# brain_system.net
KiCad netlist of a schematic drawn in EAGLE
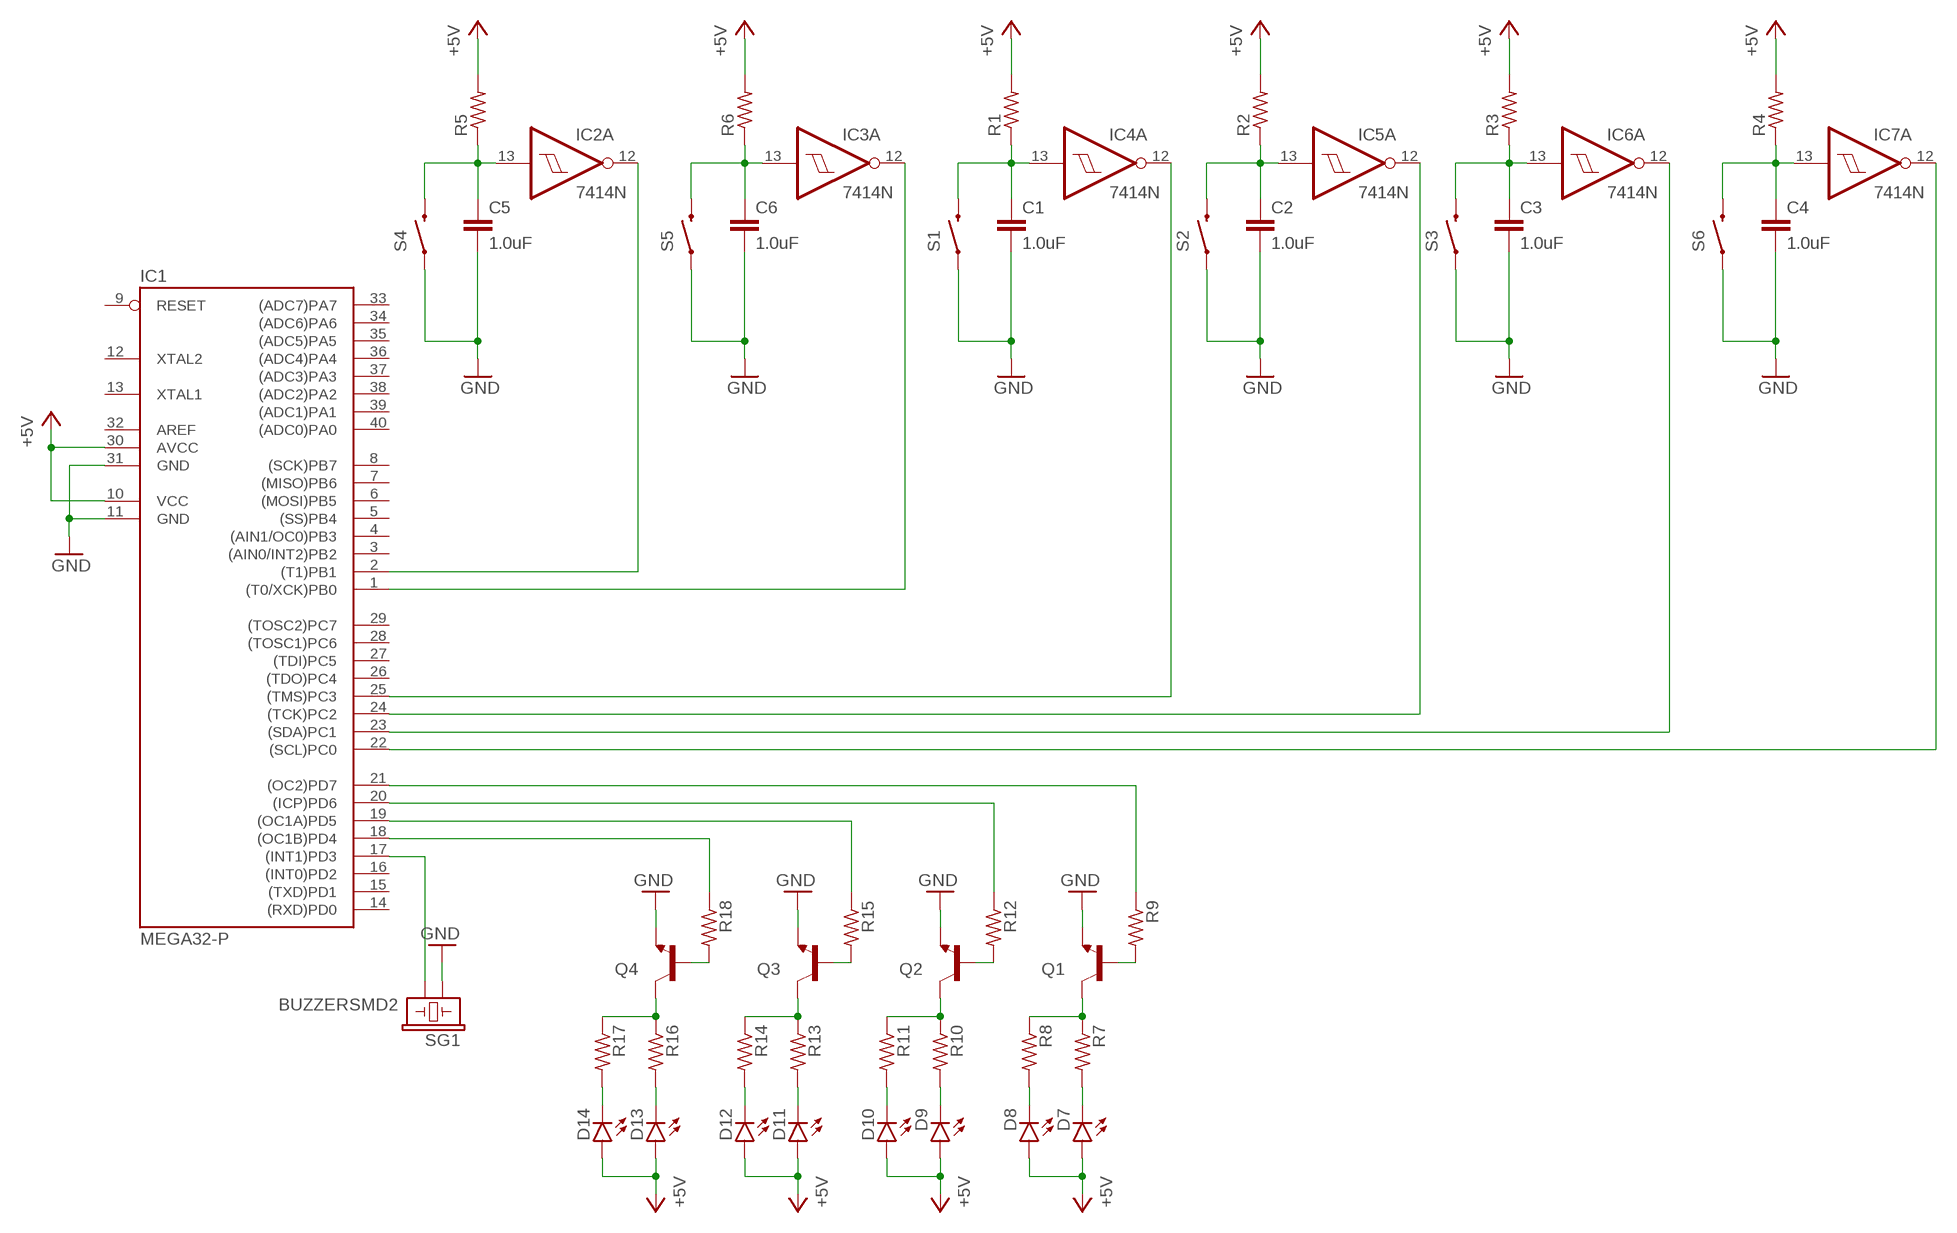
[diagram p0: schematic, sheet 1]

(export (version "E")
  (design (tool "Eeschema 10.0.6"))
  (components
    (comp (ref "C1")
      (value "1.0uF")
      (footprint "eagle-import:0402-CAP")
      (libsource (lib "eagle-import") (part "1.0UF-16V-10%(0402)"))
    )
    (comp (ref "C2")
      (value "1.0uF")
      (footprint "eagle-import:0402-CAP")
      (libsource (lib "eagle-import") (part "1.0UF-16V-10%(0402)"))
    )
    (comp (ref "C3")
      (value "1.0uF")
      (footprint "eagle-import:0402-CAP")
      (libsource (lib "eagle-import") (part "1.0UF-16V-10%(0402)"))
    )
    (comp (ref "C4")
      (value "1.0uF")
      (footprint "eagle-import:0402-CAP")
      (libsource (lib "eagle-import") (part "1.0UF-16V-10%(0402)"))
    )
    (comp (ref "C5")
      (value "1.0uF")
      (footprint "eagle-import:0402-CAP")
      (libsource (lib "eagle-import") (part "1.0UF-16V-10%(0402)"))
    )
    (comp (ref "C6")
      (value "1.0uF")
      (footprint "eagle-import:0402-CAP")
      (libsource (lib "eagle-import") (part "1.0UF-16V-10%(0402)"))
    )
    (comp (ref "D7")
      (value "LED5MM")
      (footprint "eagle-import:LED5MM")
      (libsource (lib "eagle-import") (part "LED5MM"))
    )
    (comp (ref "D8")
      (value "LED5MM")
      (footprint "eagle-import:LED5MM")
      (libsource (lib "eagle-import") (part "LED5MM"))
    )
    (comp (ref "D9")
      (value "LED5MM")
      (footprint "eagle-import:LED5MM")
      (libsource (lib "eagle-import") (part "LED5MM"))
    )
    (comp (ref "D10")
      (value "LED5MM")
      (footprint "eagle-import:LED5MM")
      (libsource (lib "eagle-import") (part "LED5MM"))
    )
    (comp (ref "D11")
      (value "LED5MM")
      (footprint "eagle-import:LED5MM")
      (libsource (lib "eagle-import") (part "LED5MM"))
    )
    (comp (ref "D12")
      (value "LED5MM")
      (footprint "eagle-import:LED5MM")
      (libsource (lib "eagle-import") (part "LED5MM"))
    )
    (comp (ref "D13")
      (value "LED5MM")
      (footprint "eagle-import:LED5MM")
      (libsource (lib "eagle-import") (part "LED5MM"))
    )
    (comp (ref "D14")
      (value "LED5MM")
      (footprint "eagle-import:LED5MM")
      (libsource (lib "eagle-import") (part "LED5MM"))
    )
    (comp (ref "IC1")
      (value "MEGA32-P")
      (footprint "eagle-import:DIL40")
      (fields (field (name "MPN") "ATMEGA32-16PU"))
      (libsource (lib "eagle-import") (part "MEGA32-P"))
    )
    (comp (ref "IC2")
      (value "7414N")
      (footprint "eagle-import:DIL14")
      (libsource (lib "eagle-import") (part "7414N"))
    )
    (comp (ref "IC3")
      (value "7414N")
      (footprint "eagle-import:DIL14")
      (libsource (lib "eagle-import") (part "7414N"))
    )
    (comp (ref "IC4")
      (value "7414N")
      (footprint "eagle-import:DIL14")
      (libsource (lib "eagle-import") (part "7414N"))
    )
    (comp (ref "IC5")
      (value "7414N")
      (footprint "eagle-import:DIL14")
      (libsource (lib "eagle-import") (part "7414N"))
    )
    (comp (ref "IC6")
      (value "7414N")
      (footprint "eagle-import:DIL14")
      (libsource (lib "eagle-import") (part "7414N"))
    )
    (comp (ref "IC7")
      (value "7414N")
      (footprint "eagle-import:DIL14")
      (libsource (lib "eagle-import") (part "7414N"))
    )
    (comp (ref "Q1")
      (value "TRANSISTOR_NPNTO92")
      (footprint "eagle-import:TO-92")
      (libsource (lib "eagle-import") (part "TRANSISTOR_NPNTO92"))
    )
    (comp (ref "Q2")
      (value "TRANSISTOR_NPNTO92")
      (footprint "eagle-import:TO-92")
      (libsource (lib "eagle-import") (part "TRANSISTOR_NPNTO92"))
    )
    (comp (ref "Q3")
      (value "TRANSISTOR_NPNTO92")
      (footprint "eagle-import:TO-92")
      (libsource (lib "eagle-import") (part "TRANSISTOR_NPNTO92"))
    )
    (comp (ref "Q4")
      (value "TRANSISTOR_NPNTO92")
      (footprint "eagle-import:TO-92")
      (libsource (lib "eagle-import") (part "TRANSISTOR_NPNTO92"))
    )
    (comp (ref "R1")
      (value "R-US_0204/5")
      (footprint "eagle-import:0204_5")
      (libsource (lib "eagle-import") (part "R-US_0204/5"))
    )
    (comp (ref "R2")
      (value "R-US_0204/5")
      (footprint "eagle-import:0204_5")
      (libsource (lib "eagle-import") (part "R-US_0204/5"))
    )
    (comp (ref "R3")
      (value "R-US_0204/5")
      (footprint "eagle-import:0204_5")
      (libsource (lib "eagle-import") (part "R-US_0204/5"))
    )
    (comp (ref "R4")
      (value "R-US_0204/5")
      (footprint "eagle-import:0204_5")
      (libsource (lib "eagle-import") (part "R-US_0204/5"))
    )
    (comp (ref "R5")
      (value "R-US_0204/5")
      (footprint "eagle-import:0204_5")
      (libsource (lib "eagle-import") (part "R-US_0204/5"))
    )
    (comp (ref "R6")
      (value "R-US_0204/5")
      (footprint "eagle-import:0204_5")
      (libsource (lib "eagle-import") (part "R-US_0204/5"))
    )
    (comp (ref "R7")
      (value "R-US_0204/5")
      (footprint "eagle-import:0204_5")
      (libsource (lib "eagle-import") (part "R-US_0204/5"))
    )
    (comp (ref "R8")
      (value "R-US_0204/5")
      (footprint "eagle-import:0204_5")
      (libsource (lib "eagle-import") (part "R-US_0204/5"))
    )
    (comp (ref "R9")
      (value "R-US_0204/5")
      (footprint "eagle-import:0204_5")
      (libsource (lib "eagle-import") (part "R-US_0204/5"))
    )
    (comp (ref "R10")
      (value "R-US_0204/5")
      (footprint "eagle-import:0204_5")
      (libsource (lib "eagle-import") (part "R-US_0204/5"))
    )
    (comp (ref "R11")
      (value "R-US_0204/5")
      (footprint "eagle-import:0204_5")
      (libsource (lib "eagle-import") (part "R-US_0204/5"))
    )
    (comp (ref "R12")
      (value "R-US_0204/5")
      (footprint "eagle-import:0204_5")
      (libsource (lib "eagle-import") (part "R-US_0204/5"))
    )
    (comp (ref "R13")
      (value "R-US_0204/5")
      (footprint "eagle-import:0204_5")
      (libsource (lib "eagle-import") (part "R-US_0204/5"))
    )
    (comp (ref "R14")
      (value "R-US_0204/5")
      (footprint "eagle-import:0204_5")
      (libsource (lib "eagle-import") (part "R-US_0204/5"))
    )
    (comp (ref "R15")
      (value "R-US_0204/5")
      (footprint "eagle-import:0204_5")
      (libsource (lib "eagle-import") (part "R-US_0204/5"))
    )
    (comp (ref "R16")
      (value "R-US_0204/5")
      (footprint "eagle-import:0204_5")
      (libsource (lib "eagle-import") (part "R-US_0204/5"))
    )
    (comp (ref "R17")
      (value "R-US_0204/5")
      (footprint "eagle-import:0204_5")
      (libsource (lib "eagle-import") (part "R-US_0204/5"))
    )
    (comp (ref "R18")
      (value "R-US_0204/5")
      (footprint "eagle-import:0204_5")
      (libsource (lib "eagle-import") (part "R-US_0204/5"))
    )
    (comp (ref "S1")
      (value "SWITCH-MOMENTARY-2PTH")
      (footprint "eagle-import:TACTILE-PTH")
      (libsource (lib "eagle-import") (part "SWITCH-MOMENTARY-2PTH"))
    )
    (comp (ref "S2")
      (value "SWITCH-MOMENTARY-2PTH")
      (footprint "eagle-import:TACTILE-PTH")
      (libsource (lib "eagle-import") (part "SWITCH-MOMENTARY-2PTH"))
    )
    (comp (ref "S3")
      (value "SWITCH-MOMENTARY-2PTH")
      (footprint "eagle-import:TACTILE-PTH")
      (libsource (lib "eagle-import") (part "SWITCH-MOMENTARY-2PTH"))
    )
    (comp (ref "S4")
      (value "SWITCH-MOMENTARY-2PTH")
      (footprint "eagle-import:TACTILE-PTH")
      (libsource (lib "eagle-import") (part "SWITCH-MOMENTARY-2PTH"))
    )
    (comp (ref "S5")
      (value "SWITCH-MOMENTARY-2PTH")
      (footprint "eagle-import:TACTILE-PTH")
      (libsource (lib "eagle-import") (part "SWITCH-MOMENTARY-2PTH"))
    )
    (comp (ref "S6")
      (value "SWITCH-MOMENTARY-2PTH")
      (footprint "eagle-import:TACTILE-PTH")
      (libsource (lib "eagle-import") (part "SWITCH-MOMENTARY-2PTH"))
    )
    (comp (ref "SG1")
      (value "BUZZERSMD2")
      (footprint "eagle-import:BUZZER-CCV")
      (libsource (lib "eagle-import") (part "BUZZERSMD2"))
    )
  )
  (nets
    (net (code "1") (name "+5V") (class "Default")
      (node (ref "D10") (pin "A") (pinfunction "A_A") (pintype "passive"))
      (node (ref "D11") (pin "A") (pinfunction "A_A") (pintype "passive"))
      (node (ref "D12") (pin "A") (pinfunction "A_A") (pintype "passive"))
      (node (ref "D13") (pin "A") (pinfunction "A_A") (pintype "passive"))
      (node (ref "D14") (pin "A") (pinfunction "A_A") (pintype "passive"))
      (node (ref "D7") (pin "A") (pinfunction "A_A") (pintype "passive"))
      (node (ref "D8") (pin "A") (pinfunction "A_A") (pintype "passive"))
      (node (ref "D9") (pin "A") (pinfunction "A_A") (pintype "passive"))
      (node (ref "IC1") (pin "10") (pinfunction "VCC_10") (pintype "power_in"))
      (node (ref "IC1") (pin "30") (pinfunction "AVCC_30") (pintype "power_in"))
      (node (ref "R1") (pin "2") (pinfunction "2_2") (pintype "passive"))
      (node (ref "R2") (pin "2") (pinfunction "2_2") (pintype "passive"))
      (node (ref "R3") (pin "2") (pinfunction "2_2") (pintype "passive"))
      (node (ref "R4") (pin "2") (pinfunction "2_2") (pintype "passive"))
      (node (ref "R5") (pin "2") (pinfunction "2_2") (pintype "passive"))
      (node (ref "R6") (pin "2") (pinfunction "2_2") (pintype "passive"))
    )
    (net (code "2") (name "GND") (class "Default")
      (node (ref "C1") (pin "2") (pinfunction "2_2") (pintype "passive"))
      (node (ref "C2") (pin "2") (pinfunction "2_2") (pintype "passive"))
      (node (ref "C3") (pin "2") (pinfunction "2_2") (pintype "passive"))
      (node (ref "C4") (pin "2") (pinfunction "2_2") (pintype "passive"))
      (node (ref "C5") (pin "2") (pinfunction "2_2") (pintype "passive"))
      (node (ref "C6") (pin "2") (pinfunction "2_2") (pintype "passive"))
      (node (ref "IC1") (pin "11") (pinfunction "GND_11") (pintype "power_in"))
      (node (ref "IC1") (pin "31") (pinfunction "GND_31") (pintype "power_in"))
      (node (ref "Q1") (pin "1") (pinfunction "E_1") (pintype "passive"))
      (node (ref "Q2") (pin "1") (pinfunction "E_1") (pintype "passive"))
      (node (ref "Q3") (pin "1") (pinfunction "E_1") (pintype "passive"))
      (node (ref "Q4") (pin "1") (pinfunction "E_1") (pintype "passive"))
      (node (ref "S1") (pin "1") (pinfunction "1_1") (pintype "passive"))
      (node (ref "S2") (pin "1") (pinfunction "1_1") (pintype "passive"))
      (node (ref "S3") (pin "1") (pinfunction "1_1") (pintype "passive"))
      (node (ref "S4") (pin "1") (pinfunction "1_1") (pintype "passive"))
      (node (ref "S5") (pin "1") (pinfunction "1_1") (pintype "passive"))
      (node (ref "S6") (pin "1") (pinfunction "1_1") (pintype "passive"))
      (node (ref "SG1") (pin "+") (pinfunction "1_+") (pintype "passive"))
    )
    (net (code "3") (name "Net-(D7-C)") (class "Default")
      (node (ref "D7") (pin "K") (pinfunction "C_K") (pintype "passive"))
      (node (ref "R7") (pin "2") (pinfunction "2_2") (pintype "passive"))
    )
    (net (code "4") (name "Net-(D8-C)") (class "Default")
      (node (ref "D8") (pin "K") (pinfunction "C_K") (pintype "passive"))
      (node (ref "R8") (pin "2") (pinfunction "2_2") (pintype "passive"))
    )
    (net (code "5") (name "Net-(D9-C)") (class "Default")
      (node (ref "D9") (pin "K") (pinfunction "C_K") (pintype "passive"))
      (node (ref "R10") (pin "2") (pinfunction "2_2") (pintype "passive"))
    )
    (net (code "6") (name "Net-(D10-C)") (class "Default")
      (node (ref "D10") (pin "K") (pinfunction "C_K") (pintype "passive"))
      (node (ref "R11") (pin "2") (pinfunction "2_2") (pintype "passive"))
    )
    (net (code "7") (name "Net-(D11-C)") (class "Default")
      (node (ref "D11") (pin "K") (pinfunction "C_K") (pintype "passive"))
      (node (ref "R13") (pin "2") (pinfunction "2_2") (pintype "passive"))
    )
    (net (code "8") (name "Net-(D12-C)") (class "Default")
      (node (ref "D12") (pin "K") (pinfunction "C_K") (pintype "passive"))
      (node (ref "R14") (pin "2") (pinfunction "2_2") (pintype "passive"))
    )
    (net (code "9") (name "Net-(D13-C)") (class "Default")
      (node (ref "D13") (pin "K") (pinfunction "C_K") (pintype "passive"))
      (node (ref "R16") (pin "2") (pinfunction "2_2") (pintype "passive"))
    )
    (net (code "10") (name "Net-(D14-C)") (class "Default")
      (node (ref "D14") (pin "K") (pinfunction "C_K") (pintype "passive"))
      (node (ref "R17") (pin "2") (pinfunction "2_2") (pintype "passive"))
    )
    (net (code "11") (name "Net-(IC1-(ICP)PD6)") (class "Default")
      (node (ref "IC1") (pin "20") (pinfunction "(ICP)PD6_20") (pintype "bidirectional"))
      (node (ref "R12") (pin "1") (pinfunction "1_1") (pintype "passive"))
    )
    (net (code "12") (name "Net-(IC1-(INT1)PD3)") (class "Default")
      (node (ref "IC1") (pin "17") (pinfunction "(INT1)PD3_17") (pintype "bidirectional"))
      (node (ref "SG1") (pin "-") (pinfunction "2_-") (pintype "passive"))
    )
    (net (code "13") (name "Net-(IC1-(OC1A)PD5)") (class "Default")
      (node (ref "IC1") (pin "19") (pinfunction "(OC1A)PD5_19") (pintype "bidirectional"))
      (node (ref "R15") (pin "1") (pinfunction "1_1") (pintype "passive"))
    )
    (net (code "14") (name "Net-(IC1-(OC1B)PD4)") (class "Default")
      (node (ref "IC1") (pin "18") (pinfunction "(OC1B)PD4_18") (pintype "bidirectional"))
      (node (ref "R18") (pin "1") (pinfunction "1_1") (pintype "passive"))
    )
    (net (code "15") (name "Net-(IC1-(OC2)PD7)") (class "Default")
      (node (ref "IC1") (pin "21") (pinfunction "(OC2)PD7_21") (pintype "bidirectional"))
      (node (ref "R9") (pin "1") (pinfunction "1_1") (pintype "passive"))
    )
    (net (code "16") (name "Net-(IC1-(SCL)PC0)") (class "Default")
      (node (ref "IC1") (pin "22") (pinfunction "(SCL)PC0_22") (pintype "bidirectional"))
      (node (ref "IC7") (pin "12") (pinfunction "O_12") (pintype "output"))
    )
    (net (code "17") (name "Net-(IC1-(SDA)PC1)") (class "Default")
      (node (ref "IC1") (pin "23") (pinfunction "(SDA)PC1_23") (pintype "bidirectional"))
      (node (ref "IC6") (pin "12") (pinfunction "O_12") (pintype "output"))
    )
    (net (code "18") (name "Net-(IC1-(T0{slash}XCK)PB0)") (class "Default")
      (node (ref "IC1") (pin "1") (pinfunction "(T0/XCK)PB0_1") (pintype "bidirectional"))
      (node (ref "IC3") (pin "12") (pinfunction "O_12") (pintype "output"))
    )
    (net (code "19") (name "Net-(IC1-(T1)PB1)") (class "Default")
      (node (ref "IC1") (pin "2") (pinfunction "(T1)PB1_2") (pintype "bidirectional"))
      (node (ref "IC2") (pin "12") (pinfunction "O_12") (pintype "output"))
    )
    (net (code "20") (name "Net-(IC1-(TCK)PC2)") (class "Default")
      (node (ref "IC1") (pin "24") (pinfunction "(TCK)PC2_24") (pintype "bidirectional"))
      (node (ref "IC5") (pin "12") (pinfunction "O_12") (pintype "output"))
    )
    (net (code "21") (name "Net-(IC1-(TMS)PC3)") (class "Default")
      (node (ref "IC1") (pin "25") (pinfunction "(TMS)PC3_25") (pintype "bidirectional"))
      (node (ref "IC4") (pin "12") (pinfunction "O_12") (pintype "output"))
    )
    (net (code "22") (name "Net-(IC2A-I)") (class "Default")
      (node (ref "C5") (pin "1") (pinfunction "1_1") (pintype "passive"))
      (node (ref "IC2") (pin "13") (pinfunction "I_13") (pintype "input"))
      (node (ref "R5") (pin "1") (pinfunction "1_1") (pintype "passive"))
      (node (ref "S4") (pin "3") (pinfunction "2_3") (pintype "passive"))
    )
    (net (code "23") (name "Net-(IC3A-I)") (class "Default")
      (node (ref "C6") (pin "1") (pinfunction "1_1") (pintype "passive"))
      (node (ref "IC3") (pin "13") (pinfunction "I_13") (pintype "input"))
      (node (ref "R6") (pin "1") (pinfunction "1_1") (pintype "passive"))
      (node (ref "S5") (pin "3") (pinfunction "2_3") (pintype "passive"))
    )
    (net (code "24") (name "Net-(IC4A-I)") (class "Default")
      (node (ref "C1") (pin "1") (pinfunction "1_1") (pintype "passive"))
      (node (ref "IC4") (pin "13") (pinfunction "I_13") (pintype "input"))
      (node (ref "R1") (pin "1") (pinfunction "1_1") (pintype "passive"))
      (node (ref "S1") (pin "3") (pinfunction "2_3") (pintype "passive"))
    )
    (net (code "25") (name "Net-(IC5A-I)") (class "Default")
      (node (ref "C2") (pin "1") (pinfunction "1_1") (pintype "passive"))
      (node (ref "IC5") (pin "13") (pinfunction "I_13") (pintype "input"))
      (node (ref "R2") (pin "1") (pinfunction "1_1") (pintype "passive"))
      (node (ref "S2") (pin "3") (pinfunction "2_3") (pintype "passive"))
    )
    (net (code "26") (name "Net-(IC6A-I)") (class "Default")
      (node (ref "C3") (pin "1") (pinfunction "1_1") (pintype "passive"))
      (node (ref "IC6") (pin "13") (pinfunction "I_13") (pintype "input"))
      (node (ref "R3") (pin "1") (pinfunction "1_1") (pintype "passive"))
      (node (ref "S3") (pin "3") (pinfunction "2_3") (pintype "passive"))
    )
    (net (code "27") (name "Net-(IC7A-I)") (class "Default")
      (node (ref "C4") (pin "1") (pinfunction "1_1") (pintype "passive"))
      (node (ref "IC7") (pin "13") (pinfunction "I_13") (pintype "input"))
      (node (ref "R4") (pin "1") (pinfunction "1_1") (pintype "passive"))
      (node (ref "S6") (pin "3") (pinfunction "2_3") (pintype "passive"))
    )
    (net (code "28") (name "Net-(Q1-B)") (class "Default")
      (node (ref "Q1") (pin "2") (pinfunction "B_2") (pintype "passive"))
      (node (ref "R9") (pin "2") (pinfunction "2_2") (pintype "passive"))
    )
    (net (code "29") (name "Net-(Q1-C)") (class "Default")
      (node (ref "Q1") (pin "3") (pinfunction "C_3") (pintype "passive"))
      (node (ref "R7") (pin "1") (pinfunction "1_1") (pintype "passive"))
      (node (ref "R8") (pin "1") (pinfunction "1_1") (pintype "passive"))
    )
    (net (code "30") (name "Net-(Q2-B)") (class "Default")
      (node (ref "Q2") (pin "2") (pinfunction "B_2") (pintype "passive"))
      (node (ref "R12") (pin "2") (pinfunction "2_2") (pintype "passive"))
    )
    (net (code "31") (name "Net-(Q2-C)") (class "Default")
      (node (ref "Q2") (pin "3") (pinfunction "C_3") (pintype "passive"))
      (node (ref "R10") (pin "1") (pinfunction "1_1") (pintype "passive"))
      (node (ref "R11") (pin "1") (pinfunction "1_1") (pintype "passive"))
    )
    (net (code "32") (name "Net-(Q3-B)") (class "Default")
      (node (ref "Q3") (pin "2") (pinfunction "B_2") (pintype "passive"))
      (node (ref "R15") (pin "2") (pinfunction "2_2") (pintype "passive"))
    )
    (net (code "33") (name "Net-(Q3-C)") (class "Default")
      (node (ref "Q3") (pin "3") (pinfunction "C_3") (pintype "passive"))
      (node (ref "R13") (pin "1") (pinfunction "1_1") (pintype "passive"))
      (node (ref "R14") (pin "1") (pinfunction "1_1") (pintype "passive"))
    )
    (net (code "34") (name "Net-(Q4-B)") (class "Default")
      (node (ref "Q4") (pin "2") (pinfunction "B_2") (pintype "passive"))
      (node (ref "R18") (pin "2") (pinfunction "2_2") (pintype "passive"))
    )
    (net (code "35") (name "Net-(Q4-C)") (class "Default")
      (node (ref "Q4") (pin "3") (pinfunction "C_3") (pintype "passive"))
      (node (ref "R16") (pin "1") (pinfunction "1_1") (pintype "passive"))
      (node (ref "R17") (pin "1") (pinfunction "1_1") (pintype "passive"))
    )
    (net (code "36") (name "unconnected-(IC1-(ADC0)PA0-Pad40)") (class "Default")
      (node (ref "IC1") (pin "40") (pinfunction "(ADC0)PA0_40") (pintype "bidirectional"))
    )
    (net (code "37") (name "unconnected-(IC1-(ADC1)PA1-Pad39)") (class "Default")
      (node (ref "IC1") (pin "39") (pinfunction "(ADC1)PA1_39") (pintype "bidirectional"))
    )
    (net (code "38") (name "unconnected-(IC1-(ADC2)PA2-Pad38)") (class "Default")
      (node (ref "IC1") (pin "38") (pinfunction "(ADC2)PA2_38") (pintype "bidirectional"))
    )
    (net (code "39") (name "unconnected-(IC1-(ADC3)PA3-Pad37)") (class "Default")
      (node (ref "IC1") (pin "37") (pinfunction "(ADC3)PA3_37") (pintype "bidirectional"))
    )
    (net (code "40") (name "unconnected-(IC1-(ADC4)PA4-Pad36)") (class "Default")
      (node (ref "IC1") (pin "36") (pinfunction "(ADC4)PA4_36") (pintype "bidirectional"))
    )
    (net (code "41") (name "unconnected-(IC1-(ADC5)PA5-Pad35)") (class "Default")
      (node (ref "IC1") (pin "35") (pinfunction "(ADC5)PA5_35") (pintype "bidirectional"))
    )
    (net (code "42") (name "unconnected-(IC1-(ADC6)PA6-Pad34)") (class "Default")
      (node (ref "IC1") (pin "34") (pinfunction "(ADC6)PA6_34") (pintype "bidirectional"))
    )
    (net (code "43") (name "unconnected-(IC1-(ADC7)PA7-Pad33)") (class "Default")
      (node (ref "IC1") (pin "33") (pinfunction "(ADC7)PA7_33") (pintype "bidirectional"))
    )
    (net (code "44") (name "unconnected-(IC1-(AIN0{slash}INT2)PB2-Pad3)") (class "Default")
      (node (ref "IC1") (pin "3") (pinfunction "(AIN0/INT2)PB2_3") (pintype "bidirectional"))
    )
    (net (code "45") (name "unconnected-(IC1-(AIN1{slash}OC0)PB3-Pad4)") (class "Default")
      (node (ref "IC1") (pin "4") (pinfunction "(AIN1/OC0)PB3_4") (pintype "bidirectional"))
    )
    (net (code "46") (name "unconnected-(IC1-(INT0)PD2-Pad16)") (class "Default")
      (node (ref "IC1") (pin "16") (pinfunction "(INT0)PD2_16") (pintype "bidirectional"))
    )
    (net (code "47") (name "unconnected-(IC1-(MISO)PB6-Pad7)") (class "Default")
      (node (ref "IC1") (pin "7") (pinfunction "(MISO)PB6_7") (pintype "bidirectional"))
    )
    (net (code "48") (name "unconnected-(IC1-(MOSI)PB5-Pad6)") (class "Default")
      (node (ref "IC1") (pin "6") (pinfunction "(MOSI)PB5_6") (pintype "bidirectional"))
    )
    (net (code "49") (name "unconnected-(IC1-(RXD)PD0-Pad14)") (class "Default")
      (node (ref "IC1") (pin "14") (pinfunction "(RXD)PD0_14") (pintype "bidirectional"))
    )
    (net (code "50") (name "unconnected-(IC1-(SCK)PB7-Pad8)") (class "Default")
      (node (ref "IC1") (pin "8") (pinfunction "(SCK)PB7_8") (pintype "bidirectional"))
    )
    (net (code "51") (name "unconnected-(IC1-(SS)PB4-Pad5)") (class "Default")
      (node (ref "IC1") (pin "5") (pinfunction "(SS)PB4_5") (pintype "bidirectional"))
    )
    (net (code "52") (name "unconnected-(IC1-(TDI)PC5-Pad27)") (class "Default")
      (node (ref "IC1") (pin "27") (pinfunction "(TDI)PC5_27") (pintype "bidirectional"))
    )
    (net (code "53") (name "unconnected-(IC1-(TDO)PC4-Pad26)") (class "Default")
      (node (ref "IC1") (pin "26") (pinfunction "(TDO)PC4_26") (pintype "bidirectional"))
    )
    (net (code "54") (name "unconnected-(IC1-(TOSC1)PC6-Pad28)") (class "Default")
      (node (ref "IC1") (pin "28") (pinfunction "(TOSC1)PC6_28") (pintype "bidirectional"))
    )
    (net (code "55") (name "unconnected-(IC1-(TOSC2)PC7-Pad29)") (class "Default")
      (node (ref "IC1") (pin "29") (pinfunction "(TOSC2)PC7_29") (pintype "bidirectional"))
    )
    (net (code "56") (name "unconnected-(IC1-(TXD)PD1-Pad15)") (class "Default")
      (node (ref "IC1") (pin "15") (pinfunction "(TXD)PD1_15") (pintype "bidirectional"))
    )
    (net (code "57") (name "unconnected-(IC1-AREF-Pad32)") (class "Default")
      (node (ref "IC1") (pin "32") (pinfunction "AREF_32") (pintype "passive"))
    )
    (net (code "58") (name "unconnected-(IC1-RESET-Pad9)") (class "Default")
      (node (ref "IC1") (pin "9") (pinfunction "RESET_9") (pintype "input"))
    )
    (net (code "59") (name "unconnected-(IC1-XTAL1-Pad13)") (class "Default")
      (node (ref "IC1") (pin "13") (pinfunction "XTAL1_13") (pintype "bidirectional"))
    )
    (net (code "60") (name "unconnected-(IC1-XTAL2-Pad12)") (class "Default")
      (node (ref "IC1") (pin "12") (pinfunction "XTAL2_12") (pintype "bidirectional"))
    )
  )
)
